# 24_067_HEAT.net
KiCad netlist of a schematic drawn in Altium Designer
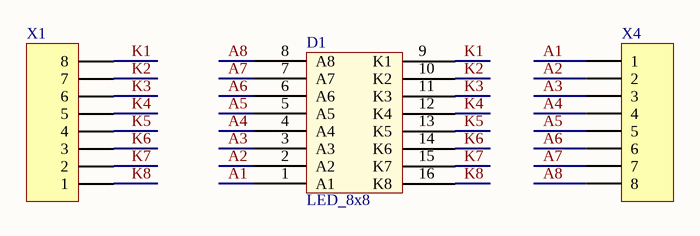
[diagram p0: 24.067_HEAT.SchDoc]

(export (version "E")
  (design (tool "Eeschema 10.0.6"))
  (components
    (comp (ref "D1") (value "LED_8x8") (footprint "LED_8x8") (libsource (lib "msp_SchLib") (part "LED_8x8")))
    (comp (ref "X1")
      (value "Header 8")
      (footprint "HDR1X8")
      (description "Header, 8-Pin")
      (fields (field (name "PUBLISHER") "Altium Limited"))
      (libsource (lib "") (part "Header 8_1"))
    )
    (comp (ref "X4")
      (value "Header 8")
      (footprint "HDR1X8")
      (description "Header, 8-Pin")
      (fields (field (name "PUBLISHER") "Altium Limited"))
      (libsource (lib "Miscellaneous Connectors") (part "Header 8"))
    )
  )
  (nets
    (net (code "1") (name "/A1") (class "Default")
      (node (ref "D1") (pin "1") (pinfunction "A1_1") (pintype "passive"))
      (node (ref "X4") (pin "1") (pinfunction "1_1") (pintype "passive"))
    )
    (net (code "2") (name "/A2") (class "Default")
      (node (ref "D1") (pin "2") (pinfunction "A2_2") (pintype "passive"))
      (node (ref "X4") (pin "2") (pinfunction "2_2") (pintype "passive"))
    )
    (net (code "3") (name "/A3") (class "Default")
      (node (ref "D1") (pin "3") (pinfunction "A3_3") (pintype "passive"))
      (node (ref "X4") (pin "3") (pinfunction "3_3") (pintype "passive"))
    )
    (net (code "4") (name "/A4") (class "Default")
      (node (ref "D1") (pin "4") (pinfunction "A4_4") (pintype "passive"))
      (node (ref "X4") (pin "4") (pinfunction "4_4") (pintype "passive"))
    )
    (net (code "5") (name "/A5") (class "Default")
      (node (ref "D1") (pin "5") (pinfunction "A5_5") (pintype "passive"))
      (node (ref "X4") (pin "5") (pinfunction "5_5") (pintype "passive"))
    )
    (net (code "6") (name "/A6") (class "Default")
      (node (ref "D1") (pin "6") (pinfunction "A6_6") (pintype "passive"))
      (node (ref "X4") (pin "6") (pinfunction "6_6") (pintype "passive"))
    )
    (net (code "7") (name "/A7") (class "Default")
      (node (ref "D1") (pin "7") (pinfunction "A7_7") (pintype "passive"))
      (node (ref "X4") (pin "7") (pinfunction "7_7") (pintype "passive"))
    )
    (net (code "8") (name "/A8") (class "Default")
      (node (ref "D1") (pin "8") (pinfunction "A8_8") (pintype "passive"))
      (node (ref "X4") (pin "8") (pinfunction "8_8") (pintype "passive"))
    )
    (net (code "9") (name "/K1") (class "Default")
      (node (ref "D1") (pin "9") (pinfunction "K1_9") (pintype "passive"))
      (node (ref "X1") (pin "8") (pinfunction "8_8") (pintype "passive"))
    )
    (net (code "10") (name "/K2") (class "Default")
      (node (ref "D1") (pin "10") (pinfunction "K2_10") (pintype "passive"))
      (node (ref "X1") (pin "7") (pinfunction "7_7") (pintype "passive"))
    )
    (net (code "11") (name "/K3") (class "Default")
      (node (ref "D1") (pin "11") (pinfunction "K3_11") (pintype "passive"))
      (node (ref "X1") (pin "6") (pinfunction "6_6") (pintype "passive"))
    )
    (net (code "12") (name "/K4") (class "Default")
      (node (ref "D1") (pin "12") (pinfunction "K4_12") (pintype "passive"))
      (node (ref "X1") (pin "5") (pinfunction "5_5") (pintype "passive"))
    )
    (net (code "13") (name "/K5") (class "Default")
      (node (ref "D1") (pin "13") (pinfunction "K5_13") (pintype "passive"))
      (node (ref "X1") (pin "4") (pinfunction "4_4") (pintype "passive"))
    )
    (net (code "14") (name "/K6") (class "Default")
      (node (ref "D1") (pin "14") (pinfunction "K6_14") (pintype "passive"))
      (node (ref "X1") (pin "3") (pinfunction "3_3") (pintype "passive"))
    )
    (net (code "15") (name "/K7") (class "Default")
      (node (ref "D1") (pin "15") (pinfunction "K7_15") (pintype "passive"))
      (node (ref "X1") (pin "2") (pinfunction "2_2") (pintype "passive"))
    )
    (net (code "16") (name "/K8") (class "Default")
      (node (ref "D1") (pin "16") (pinfunction "K8_16") (pintype "passive"))
      (node (ref "X1") (pin "1") (pinfunction "1_1") (pintype "passive"))
    )
  )
)
